# Gate_Drive.net
KiCad netlist of a schematic drawn in Altium Designer
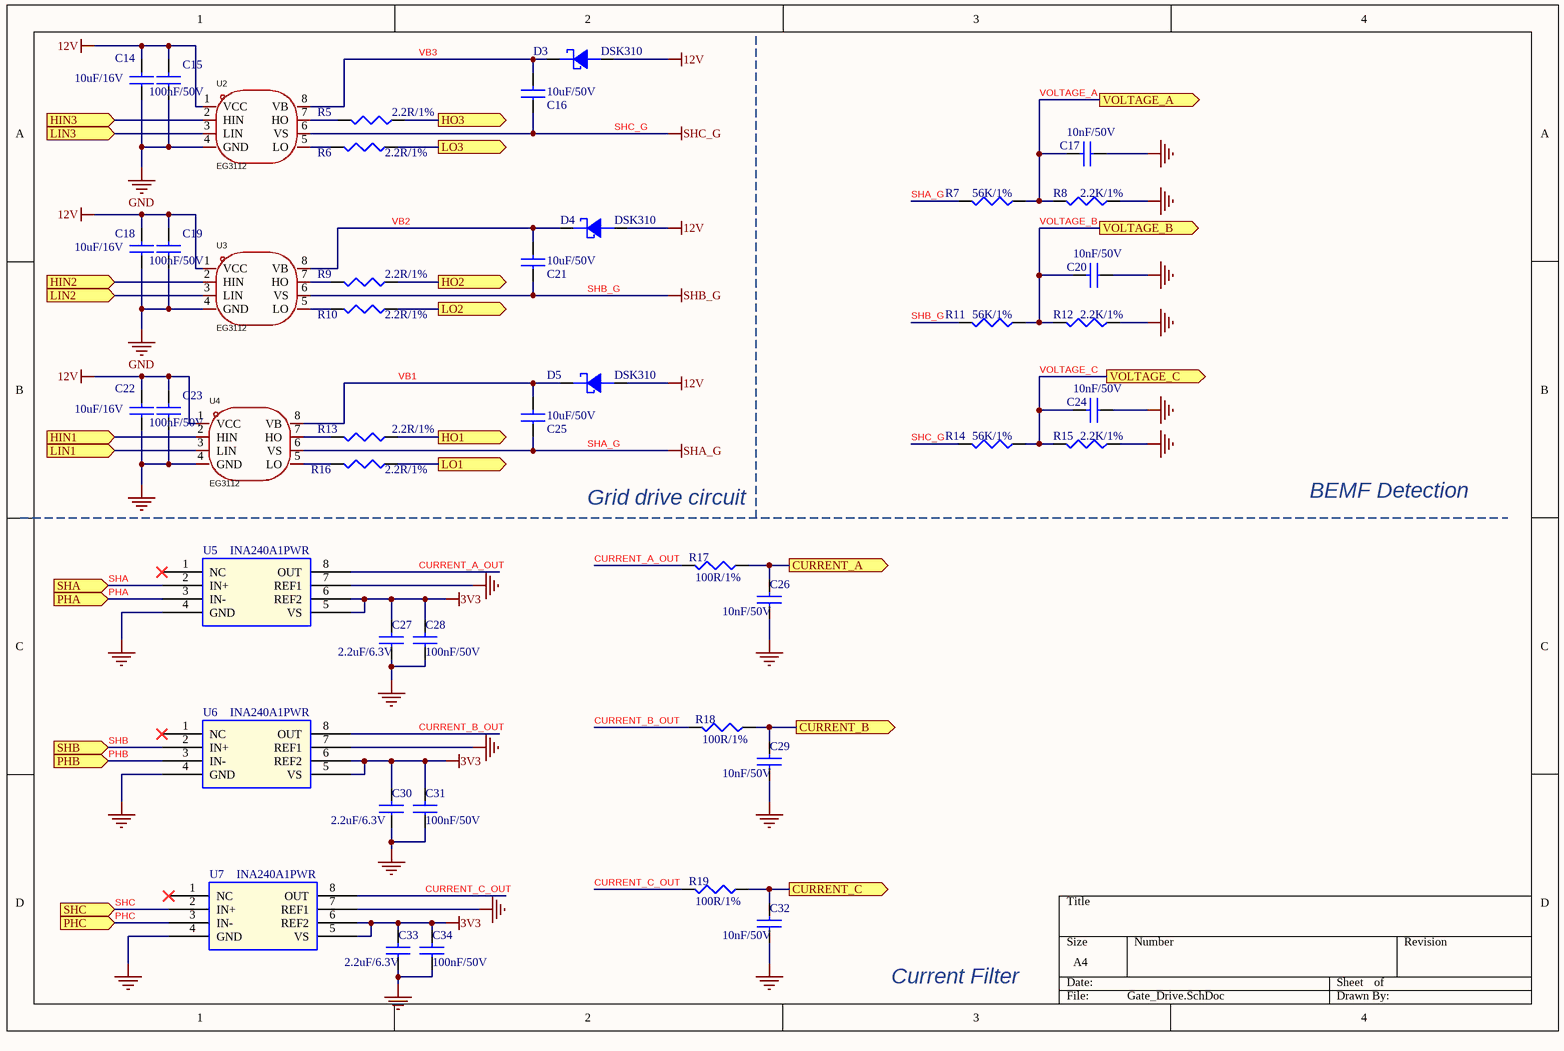
[diagram p0: Gate_Drive.SchDoc]

(export (version "E")
  (design (tool "Eeschema 10.0.6"))
  (components
    (comp (ref "C14") (value "10uF/16V") (footprint "C0603") (libsource (lib "*") (part "CAP NP")))
    (comp (ref "C15") (value "100nF/50V") (footprint "C0603") (libsource (lib "*") (part "CAP NP")))
    (comp (ref "C16") (value "10uF/50V") (footprint "C0603") (libsource (lib "*") (part "CAP NP")))
    (comp (ref "C17") (value "10nF/50V") (footprint "C0402") (libsource (lib "*") (part "CAP NP")))
    (comp (ref "C18") (value "10uF/16V") (footprint "C0603") (libsource (lib "*") (part "CAP NP")))
    (comp (ref "C19") (value "100nF/50V") (footprint "C0603") (libsource (lib "*") (part "CAP NP")))
    (comp (ref "C20") (value "10nF/50V") (footprint "C0402") (libsource (lib "*") (part "CAP NP")))
    (comp (ref "C21") (value "10uF/50V") (footprint "C0603") (libsource (lib "*") (part "CAP NP")))
    (comp (ref "C22") (value "10uF/16V") (footprint "C0603") (libsource (lib "*") (part "CAP NP")))
    (comp (ref "C23") (value "100nF/50V") (footprint "C0603") (libsource (lib "*") (part "CAP NP")))
    (comp (ref "C24") (value "10nF/50V") (footprint "C0402") (libsource (lib "*") (part "CAP NP")))
    (comp (ref "C25") (value "10uF/50V") (footprint "C0603") (libsource (lib "*") (part "CAP NP")))
    (comp (ref "C26") (value "10nF/50V") (footprint "C0402") (libsource (lib "*") (part "CAP NP")))
    (comp (ref "C27") (value "2.2uF/6.3V") (footprint "C0402") (libsource (lib "*") (part "CAP NP")))
    (comp (ref "C28") (value "100nF/50V") (footprint "C0402") (libsource (lib "*") (part "CAP NP")))
    (comp (ref "C29") (value "10nF/50V") (footprint "C0402") (libsource (lib "*") (part "CAP NP")))
    (comp (ref "C30") (value "2.2uF/6.3V") (footprint "C0402") (libsource (lib "*") (part "CAP NP")))
    (comp (ref "C31") (value "100nF/50V") (footprint "C0402") (libsource (lib "*") (part "CAP NP")))
    (comp (ref "C32") (value "10nF/50V") (footprint "C0402") (libsource (lib "*") (part "CAP NP")))
    (comp (ref "C33") (value "2.2uF/6.3V") (footprint "C0402") (libsource (lib "*") (part "CAP NP")))
    (comp (ref "C34") (value "100nF/50V") (footprint "C0402") (libsource (lib "*") (part "CAP NP")))
    (comp (ref "D3") (value "DSK310") (footprint "SOD-123F") (libsource (lib "*") (part "DIODE SCHOTTKY21")))
    (comp (ref "D4") (value "DSK310") (footprint "SOD-123F") (libsource (lib "*") (part "DIODE SCHOTTKY21")))
    (comp (ref "D5") (value "DSK310") (footprint "SOD-123F") (libsource (lib "*") (part "DIODE SCHOTTKY21")))
    (comp (ref "R5") (value "2.2R/1%") (footprint "R0603") (libsource (lib "*") (part "RESISTOR")))
    (comp (ref "R6") (value "2.2R/1%") (footprint "R0603") (libsource (lib "*") (part "RESISTOR")))
    (comp (ref "R7") (value "56K/1%") (footprint "R0402") (libsource (lib "*") (part "RESISTOR")))
    (comp (ref "R8") (value "2.2K/1%") (footprint "R0402") (libsource (lib "*") (part "RESISTOR")))
    (comp (ref "R9") (value "2.2R/1%") (footprint "R0603") (libsource (lib "*") (part "RESISTOR")))
    (comp (ref "R10") (value "2.2R/1%") (footprint "R0603") (libsource (lib "*") (part "RESISTOR")))
    (comp (ref "R11") (value "56K/1%") (footprint "R0402") (libsource (lib "*") (part "RESISTOR")))
    (comp (ref "R12") (value "2.2K/1%") (footprint "R0402") (libsource (lib "*") (part "RESISTOR")))
    (comp (ref "R13") (value "2.2R/1%") (footprint "R0603") (libsource (lib "*") (part "RESISTOR")))
    (comp (ref "R14") (value "56K/1%") (footprint "R0402") (libsource (lib "*") (part "RESISTOR")))
    (comp (ref "R15") (value "2.2K/1%") (footprint "R0402") (libsource (lib "*") (part "RESISTOR")))
    (comp (ref "R16") (value "2.2R/1%") (footprint "R0603") (libsource (lib "*") (part "RESISTOR")))
    (comp (ref "R17") (value "100R/1%") (footprint "R0402") (libsource (lib "*") (part "RESISTOR")))
    (comp (ref "R18") (value "100R/1%") (footprint "R0402") (libsource (lib "*") (part "RESISTOR")))
    (comp (ref "R19") (value "100R/1%") (footprint "R0402") (libsource (lib "*") (part "RESISTOR")))
    (comp (ref "U2")
      (value "EG3112")
      (footprint "SOIC-8_L4.9-W3.9-P1.27-LS6.0-BL")
      (fields (field (name "MANUFACTURER") "EG(屹晶微)"))
      (libsource (lib "VESC_DEVICE_Library") (part "EG3112"))
    )
    (comp (ref "U3")
      (value "EG3112")
      (footprint "SOIC-8_L4.9-W3.9-P1.27-LS6.0-BL")
      (fields (field (name "MANUFACTURER") "EG(屹晶微)"))
      (libsource (lib "VESC_DEVICE_Library") (part "EG3112"))
    )
    (comp (ref "U4")
      (value "EG3112")
      (footprint "SOIC-8_L4.9-W3.9-P1.27-LS6.0-BL")
      (fields (field (name "MANUFACTURER") "EG(屹晶微)"))
      (libsource (lib "VESC_DEVICE_Library") (part "EG3112"))
    )
    (comp (ref "U5") (value "INA240A1PWR") (footprint "TSSOP-8") (libsource (lib "*") (part "INA240A1PWR")))
    (comp (ref "U6") (value "INA240A1PWR") (footprint "TSSOP-8") (libsource (lib "*") (part "INA240A1PWR")))
    (comp (ref "U7") (value "INA240A1PWR") (footprint "TSSOP-8") (libsource (lib "*") (part "INA240A1PWR")))
  )
  (nets
    (net (code "1") (name "/CURRENT_A") (class "Default")
      (node (ref "C26") (pin "2") (pinfunction "2_2") (pintype "passive"))
      (node (ref "R17") (pin "1") (pinfunction "1_1") (pintype "passive"))
    )
    (net (code "2") (name "/CURRENT_A_OUT") (class "Default")
      (node (ref "R17") (pin "2") (pinfunction "2_2") (pintype "passive"))
      (node (ref "U5") (pin "8") (pinfunction "OUT_8") (pintype "passive"))
    )
    (net (code "3") (name "/CURRENT_B") (class "Default")
      (node (ref "C29") (pin "2") (pinfunction "2_2") (pintype "passive"))
      (node (ref "R18") (pin "1") (pinfunction "1_1") (pintype "passive"))
    )
    (net (code "4") (name "/CURRENT_B_OUT") (class "Default")
      (node (ref "R18") (pin "2") (pinfunction "2_2") (pintype "passive"))
      (node (ref "U6") (pin "8") (pinfunction "OUT_8") (pintype "passive"))
    )
    (net (code "5") (name "/CURRENT_C") (class "Default")
      (node (ref "C32") (pin "2") (pinfunction "2_2") (pintype "passive"))
      (node (ref "R19") (pin "1") (pinfunction "1_1") (pintype "passive"))
    )
    (net (code "6") (name "/CURRENT_C_OUT") (class "Default")
      (node (ref "R19") (pin "2") (pinfunction "2_2") (pintype "passive"))
      (node (ref "U7") (pin "8") (pinfunction "OUT_8") (pintype "passive"))
    )
    (net (code "7") (name "/HIN1") (class "Default")
      (node (ref "U4") (pin "2") (pinfunction "HIN_2") (pintype "passive"))
    )
    (net (code "8") (name "/HIN2") (class "Default")
      (node (ref "U3") (pin "2") (pinfunction "HIN_2") (pintype "passive"))
    )
    (net (code "9") (name "/HIN3") (class "Default")
      (node (ref "U2") (pin "2") (pinfunction "HIN_2") (pintype "passive"))
    )
    (net (code "10") (name "/HO1") (class "Default")
      (node (ref "R13") (pin "1") (pinfunction "1_1") (pintype "passive"))
    )
    (net (code "11") (name "/HO2") (class "Default")
      (node (ref "R9") (pin "1") (pinfunction "1_1") (pintype "passive"))
    )
    (net (code "12") (name "/HO3") (class "Default")
      (node (ref "R5") (pin "1") (pinfunction "1_1") (pintype "passive"))
    )
    (net (code "13") (name "/LIN1") (class "Default")
      (node (ref "U4") (pin "3") (pinfunction "LIN_3") (pintype "passive"))
    )
    (net (code "14") (name "/LIN2") (class "Default")
      (node (ref "U3") (pin "3") (pinfunction "LIN_3") (pintype "passive"))
    )
    (net (code "15") (name "/LIN3") (class "Default")
      (node (ref "U2") (pin "3") (pinfunction "LIN_3") (pintype "passive"))
    )
    (net (code "16") (name "/LO1") (class "Default")
      (node (ref "R16") (pin "1") (pinfunction "1_1") (pintype "passive"))
    )
    (net (code "17") (name "/LO2") (class "Default")
      (node (ref "R10") (pin "1") (pinfunction "1_1") (pintype "passive"))
    )
    (net (code "18") (name "/LO3") (class "Default")
      (node (ref "R6") (pin "1") (pinfunction "1_1") (pintype "passive"))
    )
    (net (code "19") (name "/PHA") (class "Default")
      (node (ref "U5") (pin "3") (pinfunction "IN-_3") (pintype "passive"))
    )
    (net (code "20") (name "/PHB") (class "Default")
      (node (ref "U6") (pin "3") (pinfunction "IN-_3") (pintype "passive"))
    )
    (net (code "21") (name "/PHC") (class "Default")
      (node (ref "U7") (pin "3") (pinfunction "IN-_3") (pintype "passive"))
    )
    (net (code "22") (name "/SHA") (class "Default")
      (node (ref "U5") (pin "2") (pinfunction "IN+_2") (pintype "passive"))
    )
    (net (code "23") (name "/SHB") (class "Default")
      (node (ref "U6") (pin "2") (pinfunction "IN+_2") (pintype "passive"))
    )
    (net (code "24") (name "/SHC") (class "Default")
      (node (ref "U7") (pin "2") (pinfunction "IN+_2") (pintype "passive"))
    )
    (net (code "25") (name "/VB1") (class "Default")
      (node (ref "C25") (pin "2") (pinfunction "2_2") (pintype "passive"))
      (node (ref "D5") (pin "1") (pinfunction "K_1") (pintype "passive"))
      (node (ref "U4") (pin "8") (pinfunction "VB_8") (pintype "passive"))
    )
    (net (code "26") (name "/VB2") (class "Default")
      (node (ref "C21") (pin "2") (pinfunction "2_2") (pintype "passive"))
      (node (ref "D4") (pin "1") (pinfunction "K_1") (pintype "passive"))
      (node (ref "U3") (pin "8") (pinfunction "VB_8") (pintype "passive"))
    )
    (net (code "27") (name "/VB3") (class "Default")
      (node (ref "C16") (pin "2") (pinfunction "2_2") (pintype "passive"))
      (node (ref "D3") (pin "1") (pinfunction "K_1") (pintype "passive"))
      (node (ref "U2") (pin "8") (pinfunction "VB_8") (pintype "passive"))
    )
    (net (code "28") (name "/VOLTAGE_A") (class "Default")
      (node (ref "C17") (pin "2") (pinfunction "2_2") (pintype "passive"))
      (node (ref "R7") (pin "1") (pinfunction "1_1") (pintype "passive"))
      (node (ref "R8") (pin "2") (pinfunction "2_2") (pintype "passive"))
    )
    (net (code "29") (name "/VOLTAGE_B") (class "Default")
      (node (ref "C20") (pin "2") (pinfunction "2_2") (pintype "passive"))
      (node (ref "R11") (pin "1") (pinfunction "1_1") (pintype "passive"))
      (node (ref "R12") (pin "2") (pinfunction "2_2") (pintype "passive"))
    )
    (net (code "30") (name "/VOLTAGE_C") (class "Default")
      (node (ref "C24") (pin "2") (pinfunction "2_2") (pintype "passive"))
      (node (ref "R14") (pin "1") (pinfunction "1_1") (pintype "passive"))
      (node (ref "R15") (pin "2") (pinfunction "2_2") (pintype "passive"))
    )
    (net (code "31") (name "3V3") (class "Default")
      (node (ref "C27") (pin "2") (pinfunction "2_2") (pintype "passive"))
      (node (ref "C28") (pin "2") (pinfunction "2_2") (pintype "passive"))
      (node (ref "C30") (pin "2") (pinfunction "2_2") (pintype "passive"))
      (node (ref "C31") (pin "2") (pinfunction "2_2") (pintype "passive"))
      (node (ref "C33") (pin "2") (pinfunction "2_2") (pintype "passive"))
      (node (ref "C34") (pin "2") (pinfunction "2_2") (pintype "passive"))
      (node (ref "U5") (pin "5") (pinfunction "VS_5") (pintype "passive"))
      (node (ref "U5") (pin "6") (pinfunction "REF2_6") (pintype "passive"))
      (node (ref "U6") (pin "5") (pinfunction "VS_5") (pintype "passive"))
      (node (ref "U6") (pin "6") (pinfunction "REF2_6") (pintype "passive"))
      (node (ref "U7") (pin "5") (pinfunction "VS_5") (pintype "passive"))
      (node (ref "U7") (pin "6") (pinfunction "REF2_6") (pintype "passive"))
    )
    (net (code "32") (name "12V") (class "Default")
      (node (ref "C14") (pin "2") (pinfunction "2_2") (pintype "passive"))
      (node (ref "C15") (pin "2") (pinfunction "2_2") (pintype "passive"))
      (node (ref "C18") (pin "2") (pinfunction "2_2") (pintype "passive"))
      (node (ref "C19") (pin "2") (pinfunction "2_2") (pintype "passive"))
      (node (ref "C22") (pin "2") (pinfunction "2_2") (pintype "passive"))
      (node (ref "C23") (pin "2") (pinfunction "2_2") (pintype "passive"))
      (node (ref "D3") (pin "2") (pinfunction "A_2") (pintype "passive"))
      (node (ref "D4") (pin "2") (pinfunction "A_2") (pintype "passive"))
      (node (ref "D5") (pin "2") (pinfunction "A_2") (pintype "passive"))
      (node (ref "U2") (pin "1") (pinfunction "VCC_1") (pintype "passive"))
      (node (ref "U3") (pin "1") (pinfunction "VCC_1") (pintype "passive"))
      (node (ref "U4") (pin "1") (pinfunction "VCC_1") (pintype "passive"))
    )
    (net (code "33") (name "GND") (class "Default")
      (node (ref "C14") (pin "1") (pinfunction "1_1") (pintype "passive"))
      (node (ref "C15") (pin "1") (pinfunction "1_1") (pintype "passive"))
      (node (ref "C17") (pin "1") (pinfunction "1_1") (pintype "passive"))
      (node (ref "C18") (pin "1") (pinfunction "1_1") (pintype "passive"))
      (node (ref "C19") (pin "1") (pinfunction "1_1") (pintype "passive"))
      (node (ref "C20") (pin "1") (pinfunction "1_1") (pintype "passive"))
      (node (ref "C22") (pin "1") (pinfunction "1_1") (pintype "passive"))
      (node (ref "C23") (pin "1") (pinfunction "1_1") (pintype "passive"))
      (node (ref "C24") (pin "1") (pinfunction "1_1") (pintype "passive"))
      (node (ref "C26") (pin "1") (pinfunction "1_1") (pintype "passive"))
      (node (ref "C27") (pin "1") (pinfunction "1_1") (pintype "passive"))
      (node (ref "C28") (pin "1") (pinfunction "1_1") (pintype "passive"))
      (node (ref "C29") (pin "1") (pinfunction "1_1") (pintype "passive"))
      (node (ref "C30") (pin "1") (pinfunction "1_1") (pintype "passive"))
      (node (ref "C31") (pin "1") (pinfunction "1_1") (pintype "passive"))
      (node (ref "C32") (pin "1") (pinfunction "1_1") (pintype "passive"))
      (node (ref "C33") (pin "1") (pinfunction "1_1") (pintype "passive"))
      (node (ref "C34") (pin "1") (pinfunction "1_1") (pintype "passive"))
      (node (ref "R12") (pin "1") (pinfunction "1_1") (pintype "passive"))
      (node (ref "R15") (pin "1") (pinfunction "1_1") (pintype "passive"))
      (node (ref "R8") (pin "1") (pinfunction "1_1") (pintype "passive"))
      (node (ref "U2") (pin "4") (pinfunction "GND_4") (pintype "passive"))
      (node (ref "U3") (pin "4") (pinfunction "GND_4") (pintype "passive"))
      (node (ref "U4") (pin "4") (pinfunction "GND_4") (pintype "passive"))
      (node (ref "U5") (pin "4") (pinfunction "GND_4") (pintype "passive"))
      (node (ref "U5") (pin "7") (pinfunction "REF1_7") (pintype "passive"))
      (node (ref "U6") (pin "4") (pinfunction "GND_4") (pintype "passive"))
      (node (ref "U6") (pin "7") (pinfunction "REF1_7") (pintype "passive"))
      (node (ref "U7") (pin "4") (pinfunction "GND_4") (pintype "passive"))
      (node (ref "U7") (pin "7") (pinfunction "REF1_7") (pintype "passive"))
    )
    (net (code "34") (name "Net-(U2-HO)") (class "Default")
      (node (ref "R5") (pin "2") (pinfunction "2_2") (pintype "passive"))
      (node (ref "U2") (pin "7") (pinfunction "HO_7") (pintype "passive"))
    )
    (net (code "35") (name "Net-(U2-LO)") (class "Default")
      (node (ref "R6") (pin "2") (pinfunction "2_2") (pintype "passive"))
      (node (ref "U2") (pin "5") (pinfunction "LO_5") (pintype "passive"))
    )
    (net (code "36") (name "Net-(U3-HO)") (class "Default")
      (node (ref "R9") (pin "2") (pinfunction "2_2") (pintype "passive"))
      (node (ref "U3") (pin "7") (pinfunction "HO_7") (pintype "passive"))
    )
    (net (code "37") (name "Net-(U3-LO)") (class "Default")
      (node (ref "R10") (pin "2") (pinfunction "2_2") (pintype "passive"))
      (node (ref "U3") (pin "5") (pinfunction "LO_5") (pintype "passive"))
    )
    (net (code "38") (name "Net-(U4-HO)") (class "Default")
      (node (ref "R13") (pin "2") (pinfunction "2_2") (pintype "passive"))
      (node (ref "U4") (pin "7") (pinfunction "HO_7") (pintype "passive"))
    )
    (net (code "39") (name "Net-(U4-LO)") (class "Default")
      (node (ref "R16") (pin "2") (pinfunction "2_2") (pintype "passive"))
      (node (ref "U4") (pin "5") (pinfunction "LO_5") (pintype "passive"))
    )
    (net (code "40") (name "SHA_G") (class "Default")
      (node (ref "C25") (pin "1") (pinfunction "1_1") (pintype "passive"))
      (node (ref "R7") (pin "2") (pinfunction "2_2") (pintype "passive"))
      (node (ref "U4") (pin "6") (pinfunction "VS_6") (pintype "passive"))
    )
    (net (code "41") (name "SHB_G") (class "Default")
      (node (ref "C21") (pin "1") (pinfunction "1_1") (pintype "passive"))
      (node (ref "R11") (pin "2") (pinfunction "2_2") (pintype "passive"))
      (node (ref "U3") (pin "6") (pinfunction "VS_6") (pintype "passive"))
    )
    (net (code "42") (name "SHC_G") (class "Default")
      (node (ref "C16") (pin "1") (pinfunction "1_1") (pintype "passive"))
      (node (ref "R14") (pin "2") (pinfunction "2_2") (pintype "passive"))
      (node (ref "U2") (pin "6") (pinfunction "VS_6") (pintype "passive"))
    )
    (net (code "43") (name "unconnected-(U5-NC-Pad1)") (class "Default")
      (node (ref "U5") (pin "1") (pinfunction "NC_1") (pintype "passive+no_connect"))
    )
    (net (code "44") (name "unconnected-(U6-NC-Pad1)") (class "Default")
      (node (ref "U6") (pin "1") (pinfunction "NC_1") (pintype "passive+no_connect"))
    )
    (net (code "45") (name "unconnected-(U7-NC-Pad1)") (class "Default")
      (node (ref "U7") (pin "1") (pinfunction "NC_1") (pintype "passive+no_connect"))
    )
  )
)
